# Modbus_TCP.net
KiCad netlist of a schematic drawn in Altium Designer
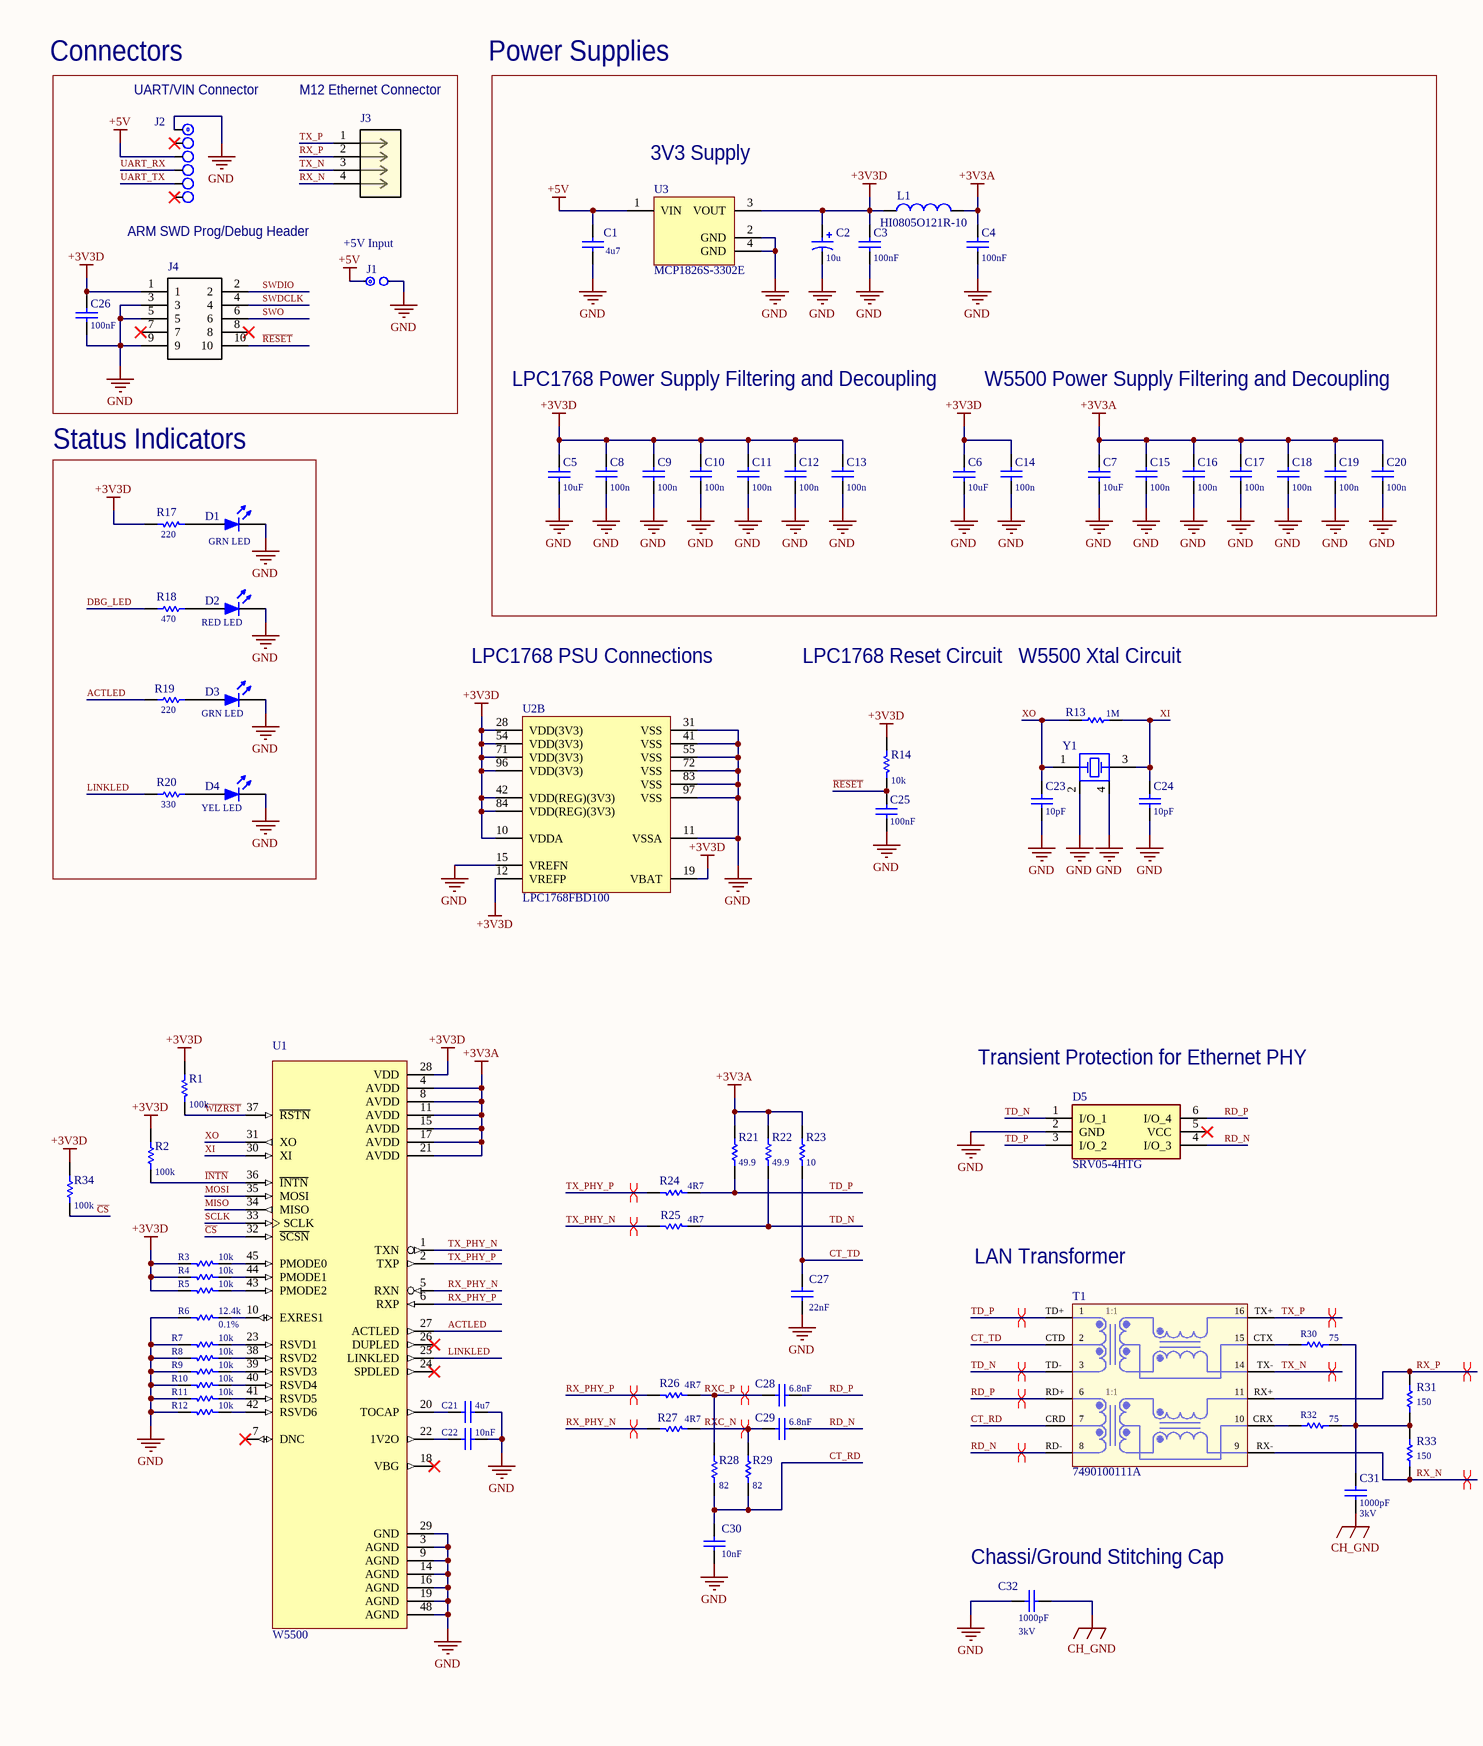
[diagram p0: Modbus TCP.SchDoc, left]
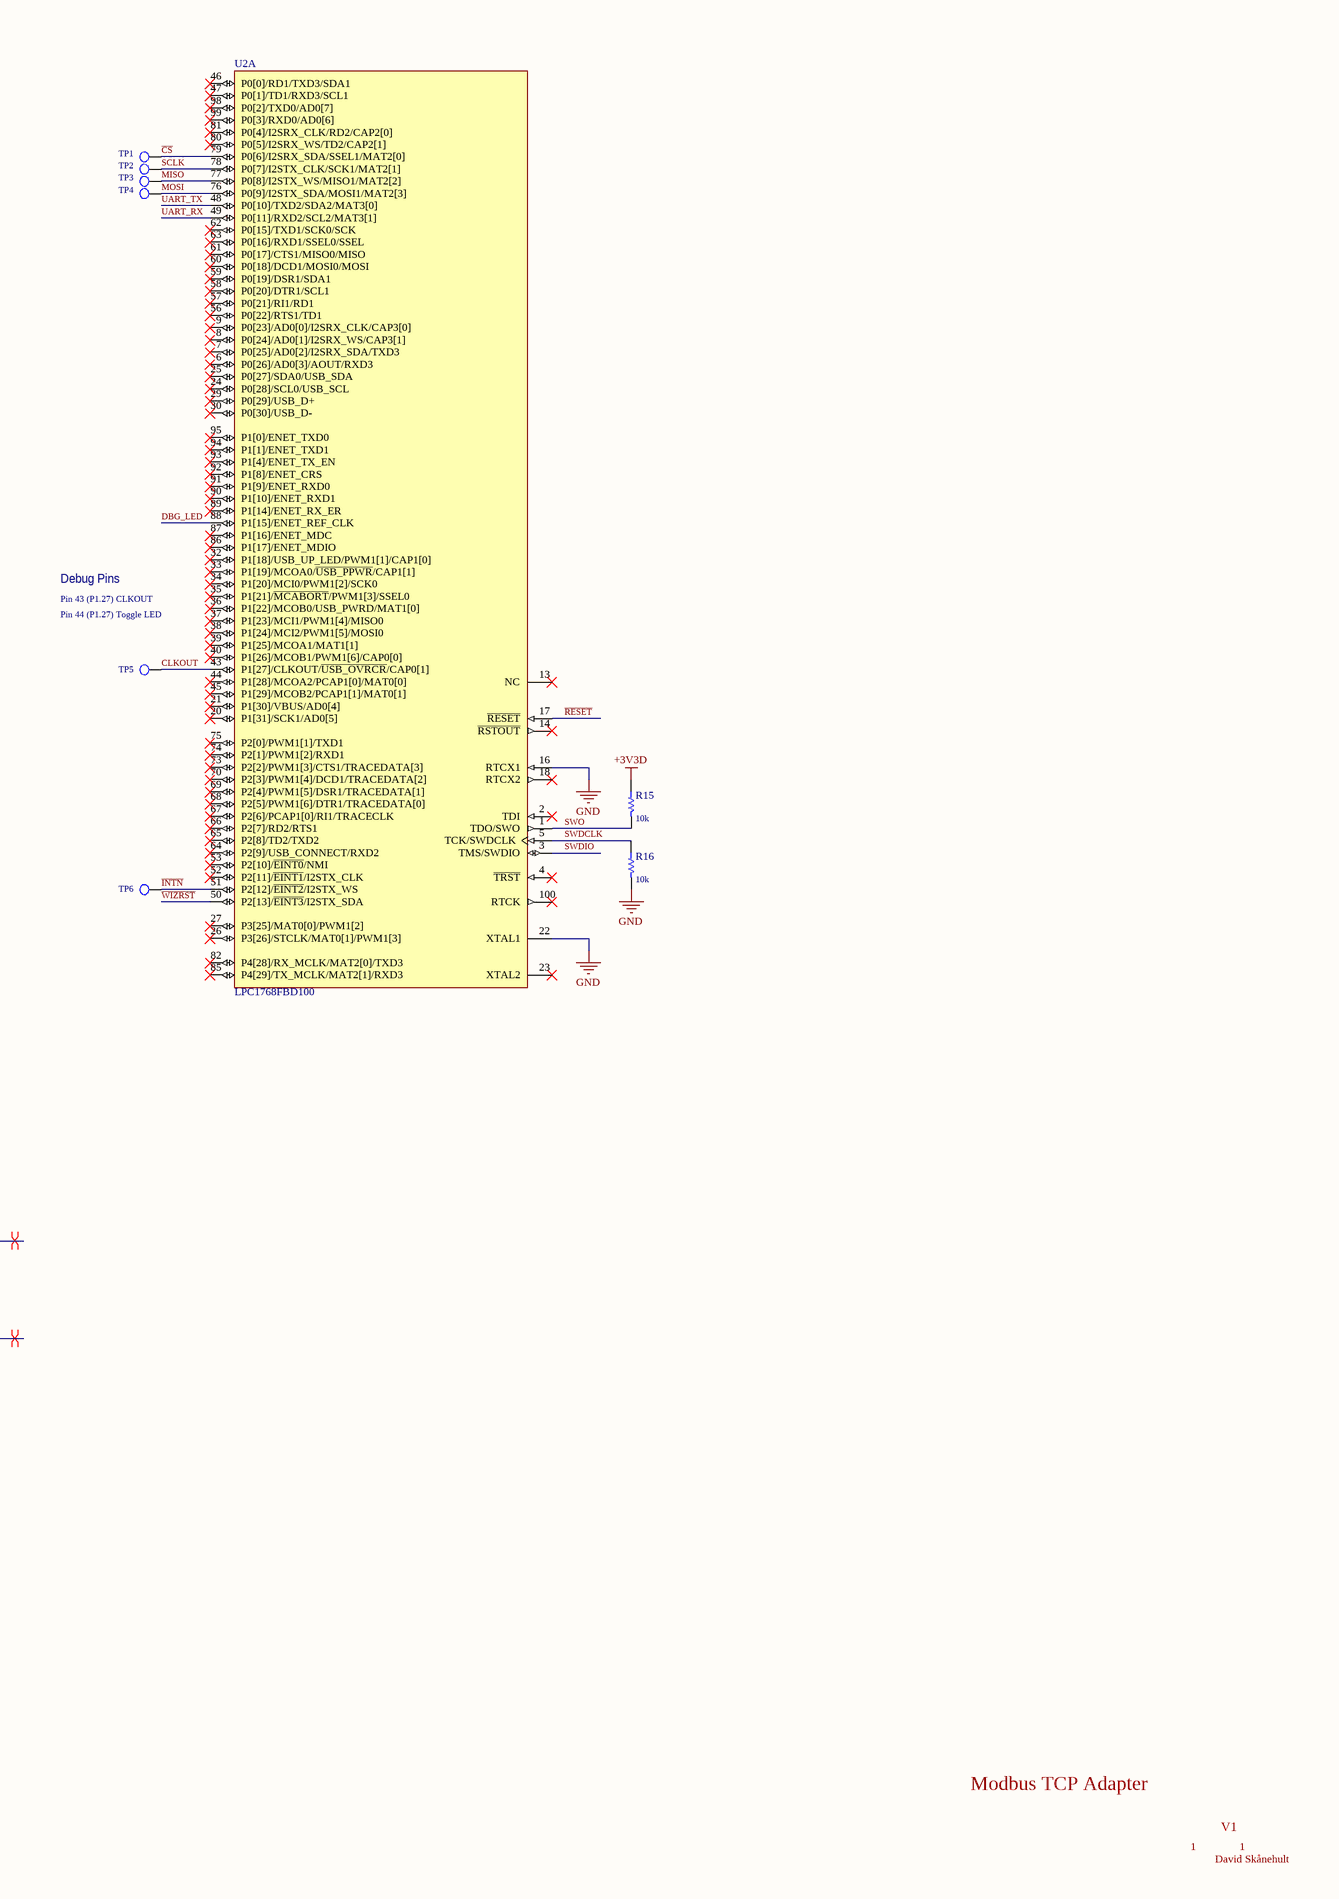
[diagram p1: Modbus TCP.SchDoc, right]

(export (version "E")
  (design (tool "Eeschema 10.0.6"))
  (components
    (comp (ref "C1")
      (value "4u7")
      (footprint "C0805C475K4RACTU")
      (description "CAP, CERM, 4.7 uF, 16 V, +/- 10%, X7R, 0805")
      (fields (field (name "PARTNUMBER") "C0805C475K4RACTU") (field (name "Comment") "CAP_0805-2012"))
      (libsource (lib "RCL") (part "CAP_0805-2012"))
    )
    (comp (ref "C2")
      (value "10u")
      (footprint "CAP3528")
      (description "CAP, TANT, 10 uF, 16 V, +/- 20%, MnO2, 3528")
      (fields
        (field (name "PARTNUMBER") "T494B106M016AT")
        (field (name "Comment") "CAP_TANT")
        (field (name "PUBLISHER") "Altium Limited")
      )
      (libsource (lib "RCL") (part "CAP_TANT"))
    )
    (comp (ref "C3")
      (value "100nF, 16V")
      (footprint "WURTH-CSGP_0402")
      (description "WCAP-CSGP General Purpose Ceramic Capacitors, size 0402, 100nF, +/-10%, 16VDC")
      (fields
        (field (name "PART NUMBER") "885012205037")
        (field (name "CAPACITANCE") "100nF")
        (field (name "PUBLISHER") "Wurth Elektronik")
      )
      (libsource (lib "WCAP-CSGP_rev19a") (part "885012205037"))
    )
    (comp (ref "C4")
      (value "100nF, 16V")
      (footprint "WURTH-CSGP_0402")
      (description "WCAP-CSGP General Purpose Ceramic Capacitors, size 0402, 100nF, +/-10%, 16VDC")
      (fields
        (field (name "PART NUMBER") "885012205037")
        (field (name "CAPACITANCE") "100nF")
        (field (name "PUBLISHER") "Wurth Elektronik")
      )
      (libsource (lib "WCAP-CSGP_rev19a") (part "885012205037"))
    )
    (comp (ref "C5")
      (value "10uF")
      (footprint "C0805C475K3RACAUTO")
      (description "CAP, CERM, 10 uF, 16 V, +/- 10%, X5R, 0805")
      (fields (field (name "PARTNUMBER") "C0805C106K4PACTU") (field (name "Comment") "CAP_0805-2012"))
      (libsource (lib "RCL") (part "CAP_0805-2012"))
    )
    (comp (ref "C6")
      (value "10uF")
      (footprint "C0805C475K3RACAUTO")
      (description "CAP, CERM, 10 uF, 16 V, +/- 10%, X5R, 0805")
      (fields (field (name "PARTNUMBER") "C0805C106K4PACTU") (field (name "Comment") "CAP_0805-2012"))
      (libsource (lib "RCL") (part "CAP_0805-2012"))
    )
    (comp (ref "C7")
      (value "10uF")
      (footprint "C0805C475K3RACAUTO")
      (description "CAP, CERM, 10 uF, 16 V, +/- 10%, X5R, 0805")
      (fields (field (name "PARTNUMBER") "C0805C106K4PACTU") (field (name "Comment") "CAP_0805-2012"))
      (libsource (lib "RCL") (part "CAP_0805-2012"))
    )
    (comp (ref "C8")
      (value "100nF, 16V")
      (footprint "WURTH-CSGP_0402")
      (description "WCAP-CSGP General Purpose Ceramic Capacitors, size 0402, 100nF, +/-10%, 16VDC")
      (fields
        (field (name "PART NUMBER") "885012205037")
        (field (name "CAPACITANCE") "100n")
        (field (name "PUBLISHER") "Wurth Elektronik")
      )
      (libsource (lib "WCAP-CSGP_rev19a") (part "885012205037"))
    )
    (comp (ref "C9")
      (value "100nF, 16V")
      (footprint "WURTH-CSGP_0402")
      (description "WCAP-CSGP General Purpose Ceramic Capacitors, size 0402, 100nF, +/-10%, 16VDC")
      (fields
        (field (name "PART NUMBER") "885012205037")
        (field (name "CAPACITANCE") "100n")
        (field (name "PUBLISHER") "Wurth Elektronik")
      )
      (libsource (lib "WCAP-CSGP_rev19a") (part "885012205037"))
    )
    (comp (ref "C10")
      (value "100nF, 16V")
      (footprint "WURTH-CSGP_0402")
      (description "WCAP-CSGP General Purpose Ceramic Capacitors, size 0402, 100nF, +/-10%, 16VDC")
      (fields
        (field (name "PART NUMBER") "885012205037")
        (field (name "CAPACITANCE") "100n")
        (field (name "PUBLISHER") "Wurth Elektronik")
      )
      (libsource (lib "WCAP-CSGP_rev19a") (part "885012205037"))
    )
    (comp (ref "C11")
      (value "100nF, 16V")
      (footprint "WURTH-CSGP_0402")
      (description "WCAP-CSGP General Purpose Ceramic Capacitors, size 0402, 100nF, +/-10%, 16VDC")
      (fields
        (field (name "PART NUMBER") "885012205037")
        (field (name "CAPACITANCE") "100n")
        (field (name "PUBLISHER") "Wurth Elektronik")
      )
      (libsource (lib "WCAP-CSGP_rev19a") (part "885012205037"))
    )
    (comp (ref "C12")
      (value "100nF, 16V")
      (footprint "WURTH-CSGP_0402")
      (description "WCAP-CSGP General Purpose Ceramic Capacitors, size 0402, 100nF, +/-10%, 16VDC")
      (fields
        (field (name "PART NUMBER") "885012205037")
        (field (name "CAPACITANCE") "100n")
        (field (name "PUBLISHER") "Wurth Elektronik")
      )
      (libsource (lib "WCAP-CSGP_rev19a") (part "885012205037"))
    )
    (comp (ref "C13")
      (value "100nF, 16V")
      (footprint "WURTH-CSGP_0402")
      (description "WCAP-CSGP General Purpose Ceramic Capacitors, size 0402, 100nF, +/-10%, 16VDC")
      (fields
        (field (name "PART NUMBER") "885012205037")
        (field (name "CAPACITANCE") "100n")
        (field (name "PUBLISHER") "Wurth Elektronik")
      )
      (libsource (lib "WCAP-CSGP_rev19a") (part "885012205037"))
    )
    (comp (ref "C14")
      (value "100nF, 16V")
      (footprint "WURTH-CSGP_0402")
      (description "WCAP-CSGP General Purpose Ceramic Capacitors, size 0402, 100nF, +/-10%, 16VDC")
      (fields
        (field (name "PART NUMBER") "885012205037")
        (field (name "CAPACITANCE") "100n")
        (field (name "PUBLISHER") "Wurth Elektronik")
      )
      (libsource (lib "WCAP-CSGP_rev19a") (part "885012205037"))
    )
    (comp (ref "C15")
      (value "100nF, 16V")
      (footprint "WURTH-CSGP_0402")
      (description "WCAP-CSGP General Purpose Ceramic Capacitors, size 0402, 100nF, +/-10%, 16VDC")
      (fields
        (field (name "PART NUMBER") "885012205037")
        (field (name "CAPACITANCE") "100n")
        (field (name "PUBLISHER") "Wurth Elektronik")
      )
      (libsource (lib "WCAP-CSGP_rev19a") (part "885012205037"))
    )
    (comp (ref "C16")
      (value "100nF, 16V")
      (footprint "WURTH-CSGP_0402")
      (description "WCAP-CSGP General Purpose Ceramic Capacitors, size 0402, 100nF, +/-10%, 16VDC")
      (fields
        (field (name "PART NUMBER") "885012205037")
        (field (name "CAPACITANCE") "100n")
        (field (name "PUBLISHER") "Wurth Elektronik")
      )
      (libsource (lib "WCAP-CSGP_rev19a") (part "885012205037"))
    )
    (comp (ref "C17")
      (value "100nF, 16V")
      (footprint "WURTH-CSGP_0402")
      (description "WCAP-CSGP General Purpose Ceramic Capacitors, size 0402, 100nF, +/-10%, 16VDC")
      (fields
        (field (name "PART NUMBER") "885012205037")
        (field (name "CAPACITANCE") "100n")
        (field (name "PUBLISHER") "Wurth Elektronik")
      )
      (libsource (lib "WCAP-CSGP_rev19a") (part "885012205037"))
    )
    (comp (ref "C18")
      (value "100nF, 16V")
      (footprint "WURTH-CSGP_0402")
      (description "WCAP-CSGP General Purpose Ceramic Capacitors, size 0402, 100nF, +/-10%, 16VDC")
      (fields
        (field (name "PART NUMBER") "885012205037")
        (field (name "CAPACITANCE") "100n")
        (field (name "PUBLISHER") "Wurth Elektronik")
      )
      (libsource (lib "WCAP-CSGP_rev19a") (part "885012205037"))
    )
    (comp (ref "C19")
      (value "100nF, 16V")
      (footprint "WURTH-CSGP_0402")
      (description "WCAP-CSGP General Purpose Ceramic Capacitors, size 0402, 100nF, +/-10%, 16VDC")
      (fields
        (field (name "PART NUMBER") "885012205037")
        (field (name "CAPACITANCE") "100n")
        (field (name "PUBLISHER") "Wurth Elektronik")
      )
      (libsource (lib "WCAP-CSGP_rev19a") (part "885012205037"))
    )
    (comp (ref "C20")
      (value "100nF, 16V")
      (footprint "WURTH-CSGP_0402")
      (description "WCAP-CSGP General Purpose Ceramic Capacitors, size 0402, 100nF, +/-10%, 16VDC")
      (fields
        (field (name "PART NUMBER") "885012205037")
        (field (name "CAPACITANCE") "100n")
        (field (name "PUBLISHER") "Wurth Elektronik")
      )
      (libsource (lib "WCAP-CSGP_rev19a") (part "885012205037"))
    )
    (comp (ref "C21")
      (value "4u7")
      (footprint "C0805C475K4RACTU")
      (description "CAP, CERM, 4.7 uF, 16 V, +/- 10%, X7R, 0805")
      (fields (field (name "PARTNUMBER") "C0805C475K4RACTU") (field (name "Comment") "CAP_0805-2012"))
      (libsource (lib "RCL") (part "CAP_0805-2012"))
    )
    (comp (ref "C22")
      (value "10nF, 25V")
      (footprint "WURTH-CSGP_0402")
      (description "WCAP-CSGP General Purpose Ceramic Capacitors, size 0402, 10nF, +/-10%, 25VDC")
      (fields
        (field (name "PART NUMBER") "885012205050")
        (field (name "CAPACITANCE") "10nF")
        (field (name "PUBLISHER") "Wurth Elektronik")
      )
      (libsource (lib "WCAP-CSGP_rev19a") (part "885012205050"))
    )
    (comp (ref "C23")
      (value "10pF, 25V")
      (footprint "WURTH-CSGP_0402")
      (description "WCAP-CSGP General Purpose Ceramic Capacitors, size 0402, 10pF, +/-5%, 25VDC")
      (fields
        (field (name "PART NUMBER") "885012005040")
        (field (name "CAPACITANCE") "10pF")
        (field (name "PUBLISHER") "Wurth Elektronik")
      )
      (libsource (lib "WCAP-CSGP_rev19a") (part "885012005040"))
    )
    (comp (ref "C24")
      (value "10pF, 25V")
      (footprint "WURTH-CSGP_0402")
      (description "WCAP-CSGP General Purpose Ceramic Capacitors, size 0402, 10pF, +/-5%, 25VDC")
      (fields
        (field (name "PART NUMBER") "885012005040")
        (field (name "CAPACITANCE") "10pF")
        (field (name "PUBLISHER") "Wurth Elektronik")
      )
      (libsource (lib "WCAP-CSGP_rev19a") (part "885012005040"))
    )
    (comp (ref "C25")
      (value "100nF, 16V")
      (footprint "WURTH-CSGP_0402")
      (description "WCAP-CSGP General Purpose Ceramic Capacitors, size 0402, 100nF, +/-10%, 16VDC")
      (fields
        (field (name "PART NUMBER") "885012205037")
        (field (name "CAPACITANCE") "100nF")
        (field (name "PUBLISHER") "Wurth Elektronik")
      )
      (libsource (lib "WCAP-CSGP_rev19a") (part "885012205037"))
    )
    (comp (ref "C26")
      (value "100nF, 16V")
      (footprint "WCAP-CSGP_0402")
      (description "WCAP-CSGP General Purpose Ceramic Capacitors, size 0402, 100nF, +/-10%, 16VDC")
      (fields
        (field (name "PART NUMBER") "885012205037")
        (field (name "CAPACITANCE") "100nF")
        (field (name "PUBLISHER") "Wurth Elektronik")
      )
      (libsource (lib "WCAP-CSGP_rev19a") (part "885012205037"))
    )
    (comp (ref "C27")
      (value "22nF, 25V")
      (footprint "WURTH-CSGP_0402")
      (description "WCAP-CSGP General Purpose Ceramic Capacitors, size 0402, 22nF, +/-10%, 25VDC")
      (fields
        (field (name "PART NUMBER") "885012205052")
        (field (name "CAPACITANCE") "22nF")
        (field (name "PUBLISHER") "Wurth Elektronik")
      )
      (libsource (lib "WCAP-CSGP_rev19a") (part "885012205052"))
    )
    (comp (ref "C28")
      (value "6.8nF, 50V")
      (footprint "WURTH-CSGP_0603_Reflow")
      (description "WCAP-CSGP General Purpose Ceramic Capacitors, size 0603, 6.8nF, +/-10%, 50VDC")
      (fields
        (field (name "PART NUMBER") "885012206088")
        (field (name "CAPACITANCE") "6.8nF")
        (field (name "PUBLISHER") "Wurth Elektronik")
      )
      (libsource (lib "WCAP-CSGP_rev19a") (part "885012206088"))
    )
    (comp (ref "C29")
      (value "6.8nF, 50V")
      (footprint "WURTH-CSGP_0603_Reflow")
      (description "WCAP-CSGP General Purpose Ceramic Capacitors, size 0603, 6.8nF, +/-10%, 50VDC")
      (fields
        (field (name "PART NUMBER") "885012206088")
        (field (name "CAPACITANCE") "6.8nF")
        (field (name "PUBLISHER") "Wurth Elektronik")
      )
      (libsource (lib "WCAP-CSGP_rev19a") (part "885012206088"))
    )
    (comp (ref "C30")
      (value "10nF, 25V")
      (footprint "WURTH-CSGP_0402")
      (description "WCAP-CSGP General Purpose Ceramic Capacitors, size 0402, 10nF, +/-10%, 25VDC")
      (fields
        (field (name "PART NUMBER") "885012205050")
        (field (name "CAPACITANCE") "10nF")
        (field (name "PUBLISHER") "Wurth Elektronik")
      )
      (libsource (lib "WCAP-CSGP_rev19a") (part "885012205050"))
    )
    (comp (ref "C31")
      (value "1000pF")
      (footprint "C1812C102KHRACTU")
      (description "CAP, CERM, 1000 pF, 3 kV, +/- 10%, X7R, 1812")
      (fields
        (field (name "VALUE2") "3kV")
        (field (name "PARTNUMBER") "C1812C102KHRACTU")
        (field (name "Comment") "CAP_1812-4532")
      )
      (libsource (lib "RCL") (part "CAP_1812-4532"))
    )
    (comp (ref "C32")
      (value "1000pF")
      (footprint "C1812C102KHRACTU")
      (description "CAP, CERM, 1000 pF, 3 kV, +/- 10%, X7R, 1812")
      (fields
        (field (name "VALUE2") "3kV")
        (field (name "PARTNUMBER") "C1812C102KHRACTU")
        (field (name "Comment") "CAP_1812-4532")
      )
      (libsource (lib "RCL") (part "CAP_1812-4532"))
    )
    (comp (ref "D1")
      (value "GRN LED")
      (footprint "KPG-1608")
      (description "KPG-1608CGKC-T")
      (fields (field (name "PUBLISHER") "Altium Limited"))
      (libsource (lib "Diodes") (part "LED"))
    )
    (comp (ref "D2")
      (value "RED LED")
      (footprint "KPG-1608")
      (description "KPG-1608SURKC-T")
      (fields (field (name "PUBLISHER") "Altium Limited"))
      (libsource (lib "Diodes") (part "LED"))
    )
    (comp (ref "D3")
      (value "GRN LED")
      (footprint "KPG-1608")
      (description "KPG-1608CGKC-T")
      (fields (field (name "PUBLISHER") "Altium Limited"))
      (libsource (lib "Diodes") (part "LED"))
    )
    (comp (ref "D4")
      (value "YEL LED")
      (footprint "KPG-1608")
      (fields (field (name "PARTNUMBER") "KPG-1608SYKC-T") (field (name "PUBLISHER") "Altium Limited"))
      (libsource (lib "Diodes") (part "LED"))
    )
    (comp (ref "D5")
      (value "SRV05-4HTG")
      (footprint "SamacSys:SOT95P280X145-6N")
      (description "TVS Diode (Uni-directional)")
      (fields (field (name "RS PART NUMBER") "7931986P"))
      (libsource (lib "*") (part "SRV05-4HTG"))
    )
    (comp (ref "J1") (value "+5V Input") (footprint "J1x2") (libsource (lib "Connektor") (part "H-1x2")))
    (comp (ref "J2")
      (value "UART/VIN Connector")
      (footprint "HR-1x6")
      (libsource (lib "Connektor") (part "HR-1x6"))
    )
    (comp (ref "J3")
      (value "M12 Ethernet Connector")
      (footprint "CONN4_T414351204")
      (description "M12,FRONT MOUNTING,FEMALE,D CODE,4P")
      (fields
        (field (name "PARTNUMBER") "T4143512041-000")
        (field (name "COPYRIGHT") "Copyright (C) 2016 Accelerated Designs. All rights reserved")
      )
      (libsource (lib "T4143512041-000") (part "T4143512041-000"))
    )
    (comp (ref "J4")
      (value "ARM SWD Prog/Debug Header")
      (footprint "*SAMTEC_FTSH-105-01-L-DV-K")
      (description "FTSH Series .050 Micro Terminal Strip")
      (fields (field (name "MF") "Samtec") (field (name "PARTNUMBER") "FTSH-105-01-L-DV-K"))
      (libsource (lib "FTSH-105-01-L-DV-K") (part "FTSH-105-01-L-DV-K"))
    )
    (comp (ref "L1")
      (value "HI0805O121R-10")
      (footprint "HI0805O121R-10")
      (description "Laird HI0805O121R-10 Ferrite Bead")
      (libsource (lib "RCL") (part "FERRITE"))
    )
    (comp (ref "R1")
      (value "100k")
      (footprint "RESC1005N - PANASONIC")
      (description "RES, 100 k, 1%, 0.1 W, 0402")
      (fields (field (name "PARTNUMBER") "ERJ2RKF1003X") (field (name "Comment") "RES_0402-1005"))
      (libsource (lib "RCL") (part "RES_0402-1005"))
    )
    (comp (ref "R2")
      (value "100k")
      (footprint "RESC1005N - PANASONIC")
      (description "RES, 100 k, 1%, 0.1 W, 0402")
      (fields (field (name "PARTNUMBER") "ERJ2RKF1003X") (field (name "Comment") "RES_0402-1005"))
      (libsource (lib "RCL") (part "RES_0402-1005"))
    )
    (comp (ref "R3")
      (value "10k")
      (footprint "RESC1005N - PANASONIC")
      (description "RES, 10 k, 1%, 0.1 W, 0402")
      (fields (field (name "PARTNUMBER") "ERJ2RKF1002X") (field (name "Comment") "RES_0402-1005"))
      (libsource (lib "RCL") (part "RES_0402-1005"))
    )
    (comp (ref "R4")
      (value "10k")
      (footprint "RESC1005N - PANASONIC")
      (description "RES, 10 k, 1%, 0.1 W, 0402")
      (fields (field (name "PARTNUMBER") "ERJ2RKF1002X") (field (name "Comment") "RES_0402-1005"))
      (libsource (lib "RCL") (part "RES_0402-1005"))
    )
    (comp (ref "R5")
      (value "10k")
      (footprint "RESC1005N - PANASONIC")
      (description "RES, 10 k, 1%, 0.1 W, 0402")
      (fields (field (name "PARTNUMBER") "ERJ2RKF1002X") (field (name "Comment") "RES_0402-1005"))
      (libsource (lib "RCL") (part "RES_0402-1005"))
    )
    (comp (ref "R6")
      (value "12.4k")
      (footprint "RESC1608N - PANASONIC ERJ")
      (description "RES, 12.4 k, 0.1%, 0.1 W, 0603")
      (fields
        (field (name "VALUE2") "0.1%")
        (field (name "PARTNUMBER") "ERA3AEB1242V")
        (field (name "Comment") "RES_0603-1608")
      )
      (libsource (lib "RCL") (part "RES_0603-1608"))
    )
    (comp (ref "R7")
      (value "10k")
      (footprint "RESC1005N - PANASONIC")
      (description "RES, 10 k, 1%, 0.1 W, 0402")
      (fields (field (name "PARTNUMBER") "ERJ2RKF1002X") (field (name "Comment") "RES_0402-1005"))
      (libsource (lib "RCL") (part "RES_0402-1005"))
    )
    (comp (ref "R8")
      (value "10k")
      (footprint "RESC1005N - PANASONIC")
      (description "RES, 10 k, 1%, 0.1 W, 0402")
      (fields (field (name "PARTNUMBER") "ERJ2RKF1002X") (field (name "Comment") "RES_0402-1005"))
      (libsource (lib "RCL") (part "RES_0402-1005"))
    )
    (comp (ref "R9")
      (value "10k")
      (footprint "RESC1005N - PANASONIC")
      (description "RES, 10 k, 1%, 0.1 W, 0402")
      (fields (field (name "PARTNUMBER") "ERJ2RKF1002X") (field (name "Comment") "RES_0402-1005"))
      (libsource (lib "RCL") (part "RES_0402-1005"))
    )
    (comp (ref "R10")
      (value "10k")
      (footprint "RESC1005N - PANASONIC")
      (description "RES, 10 k, 1%, 0.1 W, 0402")
      (fields (field (name "PARTNUMBER") "ERJ2RKF1002X") (field (name "Comment") "RES_0402-1005"))
      (libsource (lib "RCL") (part "RES_0402-1005"))
    )
    (comp (ref "R11")
      (value "10k")
      (footprint "RESC1005N - PANASONIC")
      (description "RES, 10 k, 1%, 0.1 W, 0402")
      (fields (field (name "PARTNUMBER") "ERJ2RKF1002X") (field (name "Comment") "RES_0402-1005"))
      (libsource (lib "RCL") (part "RES_0402-1005"))
    )
    (comp (ref "R12")
      (value "10k")
      (footprint "RESC1005N - PANASONIC")
      (description "RES, 10 k, 1%, 0.1 W, 0402")
      (fields (field (name "PARTNUMBER") "ERJ2RKF1002X") (field (name "Comment") "RES_0402-1005"))
      (libsource (lib "RCL") (part "RES_0402-1005"))
    )
    (comp (ref "R13")
      (value "1M")
      (footprint "RESC1005N - PANASONIC")
      (description "RES, 1 Meg, 1%, 0.1 W, 0402")
      (fields (field (name "PARTNUMBER") "ERJ2RKF1004X") (field (name "Comment") "RES_0402-1005"))
      (libsource (lib "RCL") (part "RES_0402-1005"))
    )
    (comp (ref "R14")
      (value "10k")
      (footprint "RESC1005N - PANASONIC")
      (description "RES, 10 k, 1%, 0.1 W, 0402")
      (fields (field (name "PARTNUMBER") "ERJ2RKF1002X") (field (name "Comment") "RES_0402-1005"))
      (libsource (lib "RCL") (part "RES_0402-1005"))
    )
    (comp (ref "R15")
      (value "10k")
      (footprint "RESC1005N - PANASONIC")
      (description "RES, 10 k, 1%, 0.1 W, 0402")
      (fields (field (name "PARTNUMBER") "ERJ2RKF1002X") (field (name "Comment") "RES_0402-1005"))
      (libsource (lib "RCL") (part "RES_0402-1005"))
    )
    (comp (ref "R16")
      (value "10k")
      (footprint "RESC1005N - PANASONIC")
      (description "RES, 10 k, 1%, 0.1 W, 0402")
      (fields (field (name "PARTNUMBER") "ERJ2RKF1002X") (field (name "Comment") "RES_0402-1005"))
      (libsource (lib "RCL") (part "RES_0402-1005"))
    )
    (comp (ref "R17")
      (value "220")
      (footprint "RESC1005N - PANASONIC")
      (description "RES, 220, 1%, 0.1 W, 0402")
      (fields (field (name "PARTNUMBER") "ERJ2RKF2200X") (field (name "Comment") "RES_0402-1005"))
      (libsource (lib "RCL") (part "RES_0402-1005"))
    )
    (comp (ref "R18")
      (value "470")
      (footprint "RESC1005N - PANASONIC")
      (description "RES, 470, 1%, 0.1 W, 0402")
      (fields (field (name "PARTNUMBER") "ERJ2RKF4700X") (field (name "Comment") "RES_0402-1005"))
      (libsource (lib "RCL") (part "RES_0402-1005"))
    )
    (comp (ref "R19")
      (value "220")
      (footprint "RESC1005N - PANASONIC")
      (description "RES, 220, 1%, 0.1 W, 0402")
      (fields (field (name "PARTNUMBER") "ERJ2RKF2200X") (field (name "Comment") "RES_0402-1005"))
      (libsource (lib "RCL") (part "RES_0402-1005"))
    )
    (comp (ref "R20")
      (value "330")
      (footprint "RESC1005N - PANASONIC")
      (description "RES, 220, 1%, 0.1 W, 0402")
      (fields (field (name "PARTNUMBER") "ERJ2RKF3300X") (field (name "Comment") "RES_0402-1005"))
      (libsource (lib "RCL") (part "RES_0402-1005"))
    )
    (comp (ref "R21")
      (value "49.9")
      (footprint "RESC1005N - PANASONIC")
      (description "RES, 49.9, 1%, 0.1 W, 0402")
      (fields (field (name "PARTNUMBER") "ERJ2RKF49R9X") (field (name "Comment") "RES_0402-1005"))
      (libsource (lib "RCL") (part "RES_0402-1005"))
    )
    (comp (ref "R22")
      (value "49.9")
      (footprint "RESC1005N - PANASONIC")
      (description "RES, 49.9, 1%, 0.1 W, 0402")
      (fields (field (name "PARTNUMBER") "ERJ2RKF49R9X") (field (name "Comment") "RES_0402-1005"))
      (libsource (lib "RCL") (part "RES_0402-1005"))
    )
    (comp (ref "R23")
      (value "10")
      (footprint "RESC1005N - PANASONIC")
      (description "RES, 10, 1%, 0.1 W, 0402")
      (fields (field (name "Comment") "RES_0402-1005"))
      (libsource (lib "RCL") (part "RES_0402-1005"))
    )
    (comp (ref "R24")
      (value "4R7")
      (footprint "RESC1005N - PANASONIC")
      (description "RES, 4R7, 1%, 0.1 W, 0402")
      (fields (field (name "PARTNUMBER") "CRCW04024R70FKEDHP") (field (name "Comment") "RES_0402-1005"))
      (libsource (lib "RCL") (part "RES_0402-1005"))
    )
    (comp (ref "R25")
      (value "4R7")
      (footprint "RESC1005N - PANASONIC")
      (description "RES, 4R7, 1%, 0.1 W, 0402")
      (fields (field (name "PARTNUMBER") "CRCW04024R70FKEDHP") (field (name "Comment") "RES_0402-1005"))
      (libsource (lib "RCL") (part "RES_0402-1005"))
    )
    (comp (ref "R26")
      (value "4R7")
      (footprint "RESC1005N - PANASONIC")
      (description "RES, 4R7, 1%, 0.1 W, 0402")
      (fields (field (name "PARTNUMBER") "CRCW04024R70FKEDHP") (field (name "Comment") "RES_0402-1005"))
      (libsource (lib "RCL") (part "RES_0402-1005"))
    )
    (comp (ref "R27")
      (value "4R7")
      (footprint "RESC1005N - PANASONIC")
      (description "RES, 4R7, 1%, 0.1 W, 0402")
      (fields (field (name "PARTNUMBER") "CRCW04024R70FKEDHP") (field (name "Comment") "RES_0402-1005"))
      (libsource (lib "RCL") (part "RES_0402-1005"))
    )
    (comp (ref "R28")
      (value "82")
      (footprint "RESC1005N - PANASONIC")
      (description "0402 Resistor")
      (fields (field (name "PARTNUMBER") "ERJ2RKF82R0X") (field (name "Comment") "RES_0402-1005"))
      (libsource (lib "RCL") (part "RES_0402-1005"))
    )
    (comp (ref "R29")
      (value "82")
      (footprint "RESC1005N - PANASONIC")
      (description "0402 Resistor")
      (fields (field (name "PARTNUMBER") "ERJ2RKF82R0X") (field (name "Comment") "RES_0402-1005"))
      (libsource (lib "RCL") (part "RES_0402-1005"))
    )
    (comp (ref "R30")
      (value "75")
      (footprint "RESC1608N - PANASONIC ERJ")
      (description "RES, 75, 1%, 0.1 W, 0603")
      (fields (field (name "PARTNUMBER") "CRCW060375R0FKEA") (field (name "Comment") "RES_0603-1608"))
      (libsource (lib "RCL") (part "RES_0603-1608"))
    )
    (comp (ref "R31")
      (value "150")
      (footprint "RESC1608N - PANASONIC ERJ")
      (description "RES, 150, 1%, 0.1 W, 0603")
      (fields (field (name "PARTNUMBER") "CRCW0603150RFKEA") (field (name "Comment") "RES_0603-1608"))
      (libsource (lib "RCL") (part "RES_0603-1608"))
    )
    (comp (ref "R32")
      (value "75")
      (footprint "RESC1608N - PANASONIC ERJ")
      (description "RES, 75, 1%, 0.1 W, 0603")
      (fields (field (name "PARTNUMBER") "CRCW060375R0FKEA") (field (name "Comment") "RES_0603-1608"))
      (libsource (lib "RCL") (part "RES_0603-1608"))
    )
    (comp (ref "R33")
      (value "150")
      (footprint "RESC1608N - PANASONIC ERJ")
      (description "RES, 150, 1%, 0.1 W, 0603")
      (fields (field (name "PARTNUMBER") "CRCW0603150RFKEA") (field (name "Comment") "RES_0603-1608"))
      (libsource (lib "RCL") (part "RES_0603-1608"))
    )
    (comp (ref "R34")
      (value "100k")
      (footprint "RESC1005N - PANASONIC")
      (description "RES, 100 k, 1%, 0.1 W, 0402")
      (fields (field (name "PARTNUMBER") "ERJ2RKF1003X") (field (name "Comment") "RES_0402-1005"))
      (libsource (lib "RCL") (part "RES_0402-1005"))
    )
    (comp (ref "T1")
      (value "7490100111A")
      (footprint "7490100111A")
      (description "WE-LAN LAN Transformer, SMT, 10/100 Base-T, 1 Port, non-PoE")
      (fields (field (name "PUBLISHER") "Wurth Elektronik"))
      (libsource (lib "WE-LAN") (part "7490100111A"))
    )
    (comp (ref "TP1")
      (value "Test Point")
      (footprint "TEST_PAD")
      (description "Test Pad")
      (fields (field (name "PUBLISHER") "Altium Limited"))
      (libsource (lib "Projekt2") (part "Test Point"))
    )
    (comp (ref "TP2")
      (value "Test Point")
      (footprint "TEST_PAD")
      (description "Test Pad")
      (fields (field (name "PUBLISHER") "Altium Limited"))
      (libsource (lib "Projekt2") (part "Test Point"))
    )
    (comp (ref "TP3")
      (value "Test Point")
      (footprint "TEST_PAD")
      (description "Test Pad")
      (fields (field (name "PUBLISHER") "Altium Limited"))
      (libsource (lib "Projekt2") (part "Test Point"))
    )
    (comp (ref "TP4")
      (value "Test Point")
      (footprint "TEST_PAD")
      (description "Test Pad")
      (fields (field (name "PUBLISHER") "Altium Limited"))
      (libsource (lib "Projekt2") (part "Test Point"))
    )
    (comp (ref "TP5")
      (value "Test Point")
      (footprint "TEST_PAD")
      (description "Test Pad")
      (fields (field (name "PUBLISHER") "Altium Limited"))
      (libsource (lib "Projekt2") (part "Test Point"))
    )
    (comp (ref "TP6")
      (value "Test Point")
      (footprint "TEST_PAD")
      (description "Test Pad")
      (fields (field (name "PUBLISHER") "Altium Limited"))
      (libsource (lib "Projekt2") (part "Test Point"))
    )
    (comp (ref "U1")
      (value "W5500")
      (footprint "*QFP50P900X900X160-48N")
      (description "Ethernet Controller 10/100 Base-T/TX MAC PHY SPI QFP48")
      (fields (field (name "MF") "WIZnet"))
      (libsource (lib "W5500") (part "W5500"))
    )
    (comp (ref "U2")
      (value "LPC1768FBD100")
      (footprint "SOT407-1_V")
      (libsource (lib "NXP Semiconductors Cortex-M3") (part "LPC1768FBD100"))
    )
    (comp (ref "U3")
      (value "MCP1826S-3302E")
      (footprint "SOT-223-DB3_N")
      (description "1000 mA, Low Voltage, Low Quiescent Current LDO Regulator, 3-Pin SOT-223, Extended Temperature")
      (fields (field (name "MANUFACTURER") "Microchip") (field (name "PARTNUMBER") "MCP1826S-3302E/DB"))
      (libsource (lib "Microchip Power Management Line Regulator") (part "MCP1826S-3302E/DB"))
    )
    (comp (ref "Y1")
      (value "XTAL 4-pin")
      (footprint "IQXC-42")
      (description "Crystal Oscillator")
      (fields (field (name "PARTNUMBER") "LFXTAL069494") (field (name "PUBLISHER") "Altium Limited"))
      (libsource (lib "Miscellaneous Devices") (part "XTAL 4-pin"))
    )
  )
  (nets
    (net (code "1") (name "+3V3A") (class "Default")
      (node (ref "C15") (pin "1") (pinfunction "1_1") (pintype "passive"))
      (node (ref "C16") (pin "1") (pinfunction "1_1") (pintype "passive"))
      (node (ref "C17") (pin "1") (pinfunction "1_1") (pintype "passive"))
      (node (ref "C18") (pin "1") (pinfunction "1_1") (pintype "passive"))
      (node (ref "C19") (pin "1") (pinfunction "1_1") (pintype "passive"))
      (node (ref "C20") (pin "1") (pinfunction "1_1") (pintype "passive"))
      (node (ref "C4") (pin "1") (pinfunction "1_1") (pintype "passive"))
      (node (ref "C7") (pin "1") (pinfunction "1_1") (pintype "passive"))
      (node (ref "L1") (pin "2") (pinfunction "2_2") (pintype "passive"))
      (node (ref "R21") (pin "1") (pinfunction "1_1") (pintype "passive"))
      (node (ref "R22") (pin "1") (pinfunction "1_1") (pintype "passive"))
      (node (ref "R23") (pin "1") (pinfunction "1_1") (pintype "passive"))
      (node (ref "U1") (pin "11") (pinfunction "AVDD_11") (pintype "power_in"))
      (node (ref "U1") (pin "15") (pinfunction "AVDD_15") (pintype "power_in"))
      (node (ref "U1") (pin "17") (pinfunction "AVDD_17") (pintype "power_in"))
      (node (ref "U1") (pin "21") (pinfunction "AVDD_21") (pintype "power_in"))
      (node (ref "U1") (pin "4") (pinfunction "AVDD_4") (pintype "power_in"))
      (node (ref "U1") (pin "8") (pinfunction "AVDD_8") (pintype "power_in"))
    )
    (net (code "2") (name "+3V3D") (class "Default")
      (node (ref "C10") (pin "1") (pinfunction "1_1") (pintype "passive"))
      (node (ref "C11") (pin "1") (pinfunction "1_1") (pintype "passive"))
      (node (ref "C12") (pin "1") (pinfunction "1_1") (pintype "passive"))
      (node (ref "C13") (pin "1") (pinfunction "1_1") (pintype "passive"))
      (node (ref "C14") (pin "1") (pinfunction "1_1") (pintype "passive"))
      (node (ref "C2") (pin "2") (pinfunction "2_2") (pintype "passive"))
      (node (ref "C26") (pin "1") (pinfunction "1_1") (pintype "passive"))
      (node (ref "C3") (pin "1") (pinfunction "1_1") (pintype "passive"))
      (node (ref "C5") (pin "1") (pinfunction "1_1") (pintype "passive"))
      (node (ref "C6") (pin "1") (pinfunction "1_1") (pintype "passive"))
      (node (ref "C8") (pin "1") (pinfunction "1_1") (pintype "passive"))
      (node (ref "C9") (pin "1") (pinfunction "1_1") (pintype "passive"))
      (node (ref "J4") (pin "1") (pinfunction "1_1") (pintype "passive"))
      (node (ref "L1") (pin "1") (pinfunction "1_1") (pintype "passive"))
      (node (ref "R1") (pin "1") (pinfunction "1_1") (pintype "passive"))
      (node (ref "R14") (pin "1") (pinfunction "1_1") (pintype "passive"))
      (node (ref "R15") (pin "1") (pinfunction "1_1") (pintype "passive"))
      (node (ref "R17") (pin "2") (pinfunction "2_2") (pintype "passive"))
      (node (ref "R2") (pin "1") (pinfunction "1_1") (pintype "passive"))
      (node (ref "R3") (pin "2") (pinfunction "2_2") (pintype "passive"))
      (node (ref "R34") (pin "1") (pinfunction "1_1") (pintype "passive"))
      (node (ref "R4") (pin "2") (pinfunction "2_2") (pintype "passive"))
      (node (ref "R5") (pin "2") (pinfunction "2_2") (pintype "passive"))
      (node (ref "U1") (pin "28") (pinfunction "VDD_28") (pintype "power_in"))
      (node (ref "U2") (pin "10") (pinfunction "VDDA_10") (pintype "power_in"))
      (node (ref "U2") (pin "12") (pinfunction "VREFP_12") (pintype "power_in"))
      (node (ref "U2") (pin "19") (pinfunction "VBAT_19") (pintype "power_in"))
      (node (ref "U2") (pin "28") (pinfunction "VDD(3V3)_28") (pintype "power_in"))
      (node (ref "U2") (pin "42") (pinfunction "VDD(REG)(3V3)_42") (pintype "power_in"))
      (node (ref "U2") (pin "54") (pinfunction "VDD(3V3)_54") (pintype "power_in"))
      (node (ref "U2") (pin "71") (pinfunction "VDD(3V3)_71") (pintype "power_in"))
      (node (ref "U2") (pin "84") (pinfunction "VDD(REG)(3V3)_84") (pintype "power_in"))
      (node (ref "U2") (pin "96") (pinfunction "VDD(3V3)_96") (pintype "power_in"))
      (node (ref "U3") (pin "3") (pinfunction "VOUT_3") (pintype "power_in"))
    )
    (net (code "3") (name "+5V") (class "Default")
      (node (ref "C1") (pin "1") (pinfunction "1_1") (pintype "passive"))
      (node (ref "J1") (pin "1") (pinfunction "1_1") (pintype "passive"))
      (node (ref "J2") (pin "3") (pinfunction "3_3") (pintype "passive"))
      (node (ref "U3") (pin "1") (pinfunction "VIN_1") (pintype "power_in"))
    )
    (net (code "4") (name "/ACTLED") (class "Default")
      (node (ref "R19") (pin "1") (pinfunction "1_1") (pintype "passive"))
      (node (ref "U1") (pin "27") (pinfunction "ACTLED_27") (pintype "output"))
    )
    (net (code "5") (name "/CLKOUT") (class "Default")
      (node (ref "TP5") (pin "1") (pinfunction "1_1") (pintype "passive"))
      (node (ref "U2") (pin "43") (pinfunction "P1[27]/CLKOUT/~{USB_OVRCR}/CAP0[1]_43") (pintype "bidirectional"))
    )
    (net (code "6") (name "/CT_RD") (class "Default")
      (node (ref "C30") (pin "1") (pinfunction "1_1") (pintype "passive"))
      (node (ref "R28") (pin "1") (pinfunction "1_1") (pintype "passive"))
      (node (ref "R29") (pin "1") (pinfunction "1_1") (pintype "passive"))
      (node (ref "T1") (pin "7") (pinfunction "CRD_7") (pintype "passive"))
    )
    (net (code "7") (name "/CT_TD") (class "Default")
      (node (ref "C27") (pin "1") (pinfunction "1_1") (pintype "passive"))
      (node (ref "R23") (pin "2") (pinfunction "2_2") (pintype "passive"))
      (node (ref "T1") (pin "2") (pinfunction "CTD_2") (pintype "passive"))
    )
    (net (code "8") (name "/DBG_LED") (class "Default")
      (node (ref "R18") (pin "1") (pinfunction "1_1") (pintype "passive"))
      (node (ref "U2") (pin "88") (pinfunction "P1[15]/ENET_REF_CLK_88") (pintype "bidirectional"))
    )
    (net (code "9") (name "/LINKLED") (class "Default")
      (node (ref "R20") (pin "1") (pinfunction "1_1") (pintype "passive"))
      (node (ref "U1") (pin "25") (pinfunction "LINKLED_25") (pintype "output"))
    )
    (net (code "10") (name "/MISO") (class "Default")
      (node (ref "TP3") (pin "1") (pinfunction "1_1") (pintype "passive"))
      (node (ref "U1") (pin "34") (pinfunction "MISO_34") (pintype "output"))
      (node (ref "U2") (pin "77") (pinfunction "P0[8]/I2STX_WS/MISO1/MAT2[2]_77") (pintype "bidirectional"))
    )
    (net (code "11") (name "/MOSI") (class "Default")
      (node (ref "TP4") (pin "1") (pinfunction "1_1") (pintype "passive"))
      (node (ref "U1") (pin "35") (pinfunction "MOSI_35") (pintype "input"))
      (node (ref "U2") (pin "76") (pinfunction "P0[9]/I2STX_SDA/MOSI1/MAT2[3]_76") (pintype "bidirectional"))
    )
    (net (code "12") (name "/RD_N") (class "Default")
      (node (ref "C29") (pin "2") (pinfunction "2_2") (pintype "passive"))
      (node (ref "D5") (pin "4") (pinfunction "I/O_3_4") (pintype "passive"))
      (node (ref "T1") (pin "8") (pinfunction "RD-_8") (pintype "passive"))
    )
    (net (code "13") (name "/RD_P") (class "Default")
      (node (ref "C28") (pin "2") (pinfunction "2_2") (pintype "passive"))
      (node (ref "D5") (pin "6") (pinfunction "I/O_4_6") (pintype "passive"))
      (node (ref "T1") (pin "6") (pinfunction "RD+_6") (pintype "passive"))
    )
    (net (code "14") (name "/RXC_N") (class "Default")
      (node (ref "C29") (pin "1") (pinfunction "1_1") (pintype "passive"))
      (node (ref "R27") (pin "1") (pinfunction "1_1") (pintype "passive"))
      (node (ref "R29") (pin "2") (pinfunction "2_2") (pintype "passive"))
    )
    (net (code "15") (name "/RXC_P") (class "Default")
      (node (ref "C28") (pin "1") (pinfunction "1_1") (pintype "passive"))
      (node (ref "R26") (pin "1") (pinfunction "1_1") (pintype "passive"))
      (node (ref "R28") (pin "2") (pinfunction "2_2") (pintype "passive"))
    )
    (net (code "16") (name "/RX_N") (class "Default")
      (node (ref "J3") (pin "4") (pinfunction "4_4") (pintype "passive"))
      (node (ref "R33") (pin "2") (pinfunction "2_2") (pintype "passive"))
      (node (ref "T1") (pin "9") (pinfunction "RX-_9") (pintype "passive"))
    )
    (net (code "17") (name "/RX_P") (class "Default")
      (node (ref "J3") (pin "2") (pinfunction "2_2") (pintype "passive"))
      (node (ref "R31") (pin "1") (pinfunction "1_1") (pintype "passive"))
      (node (ref "T1") (pin "11") (pinfunction "RX+_11") (pintype "passive"))
    )
    (net (code "18") (name "/RX_PHY_N") (class "Default")
      (node (ref "R27") (pin "2") (pinfunction "2_2") (pintype "passive"))
      (node (ref "U1") (pin "5") (pinfunction "RXN_5") (pintype "input"))
    )
    (net (code "19") (name "/RX_PHY_P") (class "Default")
      (node (ref "R26") (pin "2") (pinfunction "2_2") (pintype "passive"))
      (node (ref "U1") (pin "6") (pinfunction "RXP_6") (pintype "input"))
    )
    (net (code "20") (name "/SCLK") (class "Default")
      (node (ref "TP2") (pin "1") (pinfunction "1_1") (pintype "passive"))
      (node (ref "U1") (pin "33") (pinfunction "SCLK_33") (pintype "input"))
      (node (ref "U2") (pin "78") (pinfunction "P0[7]/I2STX_CLK/SCK1/MAT2[1]_78") (pintype "bidirectional"))
    )
    (net (code "21") (name "/SWDCLK") (class "Default")
      (node (ref "J4") (pin "4") (pinfunction "4_4") (pintype "passive"))
      (node (ref "R16") (pin "1") (pinfunction "1_1") (pintype "passive"))
      (node (ref "U2") (pin "5") (pinfunction "TCK/SWDCLK_5") (pintype "input"))
    )
    (net (code "22") (name "/SWDIO") (class "Default")
      (node (ref "J4") (pin "2") (pinfunction "2_2") (pintype "passive"))
      (node (ref "U2") (pin "3") (pinfunction "TMS/SWDIO_3") (pintype "bidirectional"))
    )
    (net (code "23") (name "/SWO") (class "Default")
      (node (ref "J4") (pin "6") (pinfunction "6_6") (pintype "passive"))
      (node (ref "R15") (pin "2") (pinfunction "2_2") (pintype "passive"))
      (node (ref "U2") (pin "1") (pinfunction "TDO/SWO_1") (pintype "output"))
    )
    (net (code "24") (name "/TD_N") (class "Default")
      (node (ref "D5") (pin "1") (pinfunction "I/O_1_1") (pintype "passive"))
      (node (ref "R22") (pin "2") (pinfunction "2_2") (pintype "passive"))
      (node (ref "R25") (pin "1") (pinfunction "1_1") (pintype "passive"))
      (node (ref "T1") (pin "3") (pinfunction "TD-_3") (pintype "passive"))
    )
    (net (code "25") (name "/TD_P") (class "Default")
      (node (ref "D5") (pin "3") (pinfunction "I/O_2_3") (pintype "passive"))
      (node (ref "R21") (pin "2") (pinfunction "2_2") (pintype "passive"))
      (node (ref "R24") (pin "1") (pinfunction "1_1") (pintype "passive"))
      (node (ref "T1") (pin "1") (pinfunction "TD+_1") (pintype "passive"))
    )
    (net (code "26") (name "/TX_N") (class "Default")
      (node (ref "J3") (pin "3") (pinfunction "3_3") (pintype "passive"))
      (node (ref "T1") (pin "14") (pinfunction "TX-_14") (pintype "passive"))
    )
    (net (code "27") (name "/TX_P") (class "Default")
      (node (ref "J3") (pin "1") (pinfunction "1_1") (pintype "passive"))
      (node (ref "T1") (pin "16") (pinfunction "TX+_16") (pintype "passive"))
    )
    (net (code "28") (name "/TX_PHY_N") (class "Default")
      (node (ref "R25") (pin "2") (pinfunction "2_2") (pintype "passive"))
      (node (ref "U1") (pin "1") (pinfunction "TXN_1") (pintype "output"))
    )
    (net (code "29") (name "/TX_PHY_P") (class "Default")
      (node (ref "R24") (pin "2") (pinfunction "2_2") (pintype "passive"))
      (node (ref "U1") (pin "2") (pinfunction "TXP_2") (pintype "output"))
    )
    (net (code "30") (name "/UART_RX") (class "Default")
      (node (ref "J2") (pin "4") (pinfunction "4_4") (pintype "passive"))
      (node (ref "U2") (pin "49") (pinfunction "P0[11]/RXD2/SCL2/MAT3[1]_49") (pintype "bidirectional"))
    )
    (net (code "31") (name "/UART_TX") (class "Default")
      (node (ref "J2") (pin "5") (pinfunction "5_5") (pintype "passive"))
      (node (ref "U2") (pin "48") (pinfunction "P0[10]/TXD2/SDA2/MAT3[0]_48") (pintype "bidirectional"))
    )
    (net (code "32") (name "/XI") (class "Default")
      (node (ref "C24") (pin "1") (pinfunction "1_1") (pintype "passive"))
      (node (ref "R13") (pin "1") (pinfunction "1_1") (pintype "passive"))
      (node (ref "U1") (pin "30") (pinfunction "XI_30") (pintype "input"))
      (node (ref "Y1") (pin "3") (pinfunction "OSC2_3") (pintype "passive"))
    )
    (net (code "33") (name "/XO") (class "Default")
      (node (ref "C23") (pin "1") (pinfunction "1_1") (pintype "passive"))
      (node (ref "R13") (pin "2") (pinfunction "2_2") (pintype "passive"))
      (node (ref "U1") (pin "31") (pinfunction "XO_31") (pintype "output"))
      (node (ref "Y1") (pin "1") (pinfunction "OSC1_1") (pintype "passive"))
    )
    (net (code "34") (name "/~{CS}") (class "Default")
      (node (ref "R34") (pin "2") (pinfunction "2_2") (pintype "passive"))
      (node (ref "TP1") (pin "1") (pinfunction "1_1") (pintype "passive"))
      (node (ref "U1") (pin "32") (pinfunction "~{SCSN}_32") (pintype "input"))
      (node (ref "U2") (pin "79") (pinfunction "P0[6]/I2SRX_SDA/SSEL1/MAT2[0]_79") (pintype "bidirectional"))
    )
    (net (code "35") (name "/~{INTN}") (class "Default")
      (node (ref "R2") (pin "2") (pinfunction "2_2") (pintype "passive"))
      (node (ref "TP6") (pin "1") (pinfunction "1_1") (pintype "passive"))
      (node (ref "U1") (pin "36") (pinfunction "~{INTN}_36") (pintype "input"))
      (node (ref "U2") (pin "51") (pinfunction "P2[12]/~{EINT2}/I2STX_WS_51") (pintype "bidirectional"))
    )
    (net (code "36") (name "/~{RESET}") (class "Default")
      (node (ref "C25") (pin "1") (pinfunction "1_1") (pintype "passive"))
      (node (ref "J4") (pin "10") (pinfunction "10_10") (pintype "passive"))
      (node (ref "R14") (pin "2") (pinfunction "2_2") (pintype "passive"))
      (node (ref "U2") (pin "17") (pinfunction "~{RESET}_17") (pintype "input"))
    )
    (net (code "37") (name "/~{WIZRST}") (class "Default")
      (node (ref "R1") (pin "2") (pinfunction "2_2") (pintype "passive"))
      (node (ref "U1") (pin "37") (pinfunction "~{RSTN}_37") (pintype "input"))
      (node (ref "U2") (pin "50") (pinfunction "P2[13]/~{EINT3}/I2STX_SDA_50") (pintype "bidirectional"))
    )
    (net (code "38") (name "CH_GND") (class "Default")
      (node (ref "C31") (pin "2") (pinfunction "2_2") (pintype "passive"))
      (node (ref "C32") (pin "2") (pinfunction "2_2") (pintype "passive"))
    )
    (net (code "39") (name "GND") (class "Default")
      (node (ref "C1") (pin "2") (pinfunction "2_2") (pintype "passive"))
      (node (ref "C10") (pin "2") (pinfunction "2_2") (pintype "passive"))
      (node (ref "C11") (pin "2") (pinfunction "2_2") (pintype "passive"))
      (node (ref "C12") (pin "2") (pinfunction "2_2") (pintype "passive"))
      (node (ref "C13") (pin "2") (pinfunction "2_2") (pintype "passive"))
      (node (ref "C14") (pin "2") (pinfunction "2_2") (pintype "passive"))
      (node (ref "C15") (pin "2") (pinfunction "2_2") (pintype "passive"))
      (node (ref "C16") (pin "2") (pinfunction "2_2") (pintype "passive"))
      (node (ref "C17") (pin "2") (pinfunction "2_2") (pintype "passive"))
      (node (ref "C18") (pin "2") (pinfunction "2_2") (pintype "passive"))
      (node (ref "C19") (pin "2") (pinfunction "2_2") (pintype "passive"))
      (node (ref "C2") (pin "1") (pinfunction "1_1") (pintype "passive"))
      (node (ref "C20") (pin "2") (pinfunction "2_2") (pintype "passive"))
      (node (ref "C21") (pin "2") (pinfunction "2_2") (pintype "passive"))
      (node (ref "C22") (pin "2") (pinfunction "2_2") (pintype "passive"))
      (node (ref "C23") (pin "2") (pinfunction "2_2") (pintype "passive"))
      (node (ref "C24") (pin "2") (pinfunction "2_2") (pintype "passive"))
      (node (ref "C25") (pin "2") (pinfunction "2_2") (pintype "passive"))
      (node (ref "C26") (pin "2") (pinfunction "2_2") (pintype "passive"))
      (node (ref "C27") (pin "2") (pinfunction "2_2") (pintype "passive"))
      (node (ref "C3") (pin "2") (pinfunction "2_2") (pintype "passive"))
      (node (ref "C30") (pin "2") (pinfunction "2_2") (pintype "passive"))
      (node (ref "C32") (pin "1") (pinfunction "1_1") (pintype "passive"))
      (node (ref "C4") (pin "2") (pinfunction "2_2") (pintype "passive"))
      (node (ref "C5") (pin "2") (pinfunction "2_2") (pintype "passive"))
      (node (ref "C6") (pin "2") (pinfunction "2_2") (pintype "passive"))
      (node (ref "C7") (pin "2") (pinfunction "2_2") (pintype "passive"))
      (node (ref "C8") (pin "2") (pinfunction "2_2") (pintype "passive"))
      (node (ref "C9") (pin "2") (pinfunction "2_2") (pintype "passive"))
      (node (ref "D1") (pin "2") (pinfunction "K_2") (pintype "passive"))
      (node (ref "D2") (pin "2") (pinfunction "K_2") (pintype "passive"))
      (node (ref "D3") (pin "2") (pinfunction "K_2") (pintype "passive"))
      (node (ref "D4") (pin "2") (pinfunction "K_2") (pintype "passive"))
      (node (ref "D5") (pin "2") (pinfunction "GND_2") (pintype "passive"))
      (node (ref "J1") (pin "2") (pinfunction "2_2") (pintype "passive"))
      (node (ref "J2") (pin "1") (pinfunction "1_1") (pintype "passive"))
      (node (ref "J4") (pin "3") (pinfunction "3_3") (pintype "passive"))
      (node (ref "J4") (pin "5") (pinfunction "5_5") (pintype "passive"))
      (node (ref "J4") (pin "9") (pinfunction "9_9") (pintype "passive"))
      (node (ref "R10") (pin "2") (pinfunction "2_2") (pintype "passive"))
      (node (ref "R11") (pin "2") (pinfunction "2_2") (pintype "passive"))
      (node (ref "R12") (pin "2") (pinfunction "2_2") (pintype "passive"))
      (node (ref "R16") (pin "2") (pinfunction "2_2") (pintype "passive"))
      (node (ref "R6") (pin "2") (pinfunction "2_2") (pintype "passive"))
      (node (ref "R7") (pin "2") (pinfunction "2_2") (pintype "passive"))
      (node (ref "R8") (pin "2") (pinfunction "2_2") (pintype "passive"))
      (node (ref "R9") (pin "2") (pinfunction "2_2") (pintype "passive"))
      (node (ref "U1") (pin "14") (pinfunction "AGND_14") (pintype "power_in"))
      (node (ref "U1") (pin "16") (pinfunction "AGND_16") (pintype "power_in"))
      (node (ref "U1") (pin "19") (pinfunction "AGND_19") (pintype "power_in"))
      (node (ref "U1") (pin "29") (pinfunction "GND_29") (pintype "passive"))
      (node (ref "U1") (pin "3") (pinfunction "AGND_3") (pintype "power_in"))
      (node (ref "U1") (pin "48") (pinfunction "AGND_48") (pintype "power_in"))
      (node (ref "U1") (pin "9") (pinfunction "AGND_9") (pintype "power_in"))
      (node (ref "U2") (pin "11") (pinfunction "VSSA_11") (pintype "power_in"))
      (node (ref "U2") (pin "15") (pinfunction "VREFN_15") (pintype "power_in"))
      (node (ref "U2") (pin "16") (pinfunction "RTCX1_16") (pintype "input"))
      (node (ref "U2") (pin "22") (pinfunction "XTAL1_22") (pintype "passive"))
      (node (ref "U2") (pin "31") (pinfunction "VSS_31") (pintype "power_in"))
      (node (ref "U2") (pin "41") (pinfunction "VSS_41") (pintype "power_in"))
      (node (ref "U2") (pin "55") (pinfunction "VSS_55") (pintype "power_in"))
      (node (ref "U2") (pin "72") (pinfunction "VSS_72") (pintype "power_in"))
      (node (ref "U2") (pin "83") (pinfunction "VSS_83") (pintype "power_in"))
      (node (ref "U2") (pin "97") (pinfunction "VSS_97") (pintype "power_in"))
      (node (ref "U3") (pin "2") (pinfunction "GND_2") (pintype "power_in"))
      (node (ref "U3") (pin "4") (pinfunction "GND_4") (pintype "power_in"))
      (node (ref "Y1") (pin "2") (pinfunction "GND1_2") (pintype "passive"))
      (node (ref "Y1") (pin "4") (pinfunction "GND2_4") (pintype "passive"))
    )
    (net (code "40") (name "Net-(C31-Pad1)") (class "Default")
      (node (ref "C31") (pin "1") (pinfunction "1_1") (pintype "passive"))
      (node (ref "R30") (pin "2") (pinfunction "2_2") (pintype "passive"))
      (node (ref "R31") (pin "2") (pinfunction "2_2") (pintype "passive"))
      (node (ref "R32") (pin "2") (pinfunction "2_2") (pintype "passive"))
      (node (ref "R33") (pin "1") (pinfunction "1_1") (pintype "passive"))
    )
    (net (code "41") (name "Net-(D1-A)") (class "Default")
      (node (ref "D1") (pin "1") (pinfunction "A_1") (pintype "passive"))
      (node (ref "R17") (pin "1") (pinfunction "1_1") (pintype "passive"))
    )
    (net (code "42") (name "Net-(D2-A)") (class "Default")
      (node (ref "D2") (pin "1") (pinfunction "A_1") (pintype "passive"))
      (node (ref "R18") (pin "2") (pinfunction "2_2") (pintype "passive"))
    )
    (net (code "43") (name "Net-(D3-A)") (class "Default")
      (node (ref "D3") (pin "1") (pinfunction "A_1") (pintype "passive"))
      (node (ref "R19") (pin "2") (pinfunction "2_2") (pintype "passive"))
    )
    (net (code "44") (name "Net-(D4-A)") (class "Default")
      (node (ref "D4") (pin "1") (pinfunction "A_1") (pintype "passive"))
      (node (ref "R20") (pin "2") (pinfunction "2_2") (pintype "passive"))
    )
    (net (code "45") (name "Net-(T1-CRX)") (class "Default")
      (node (ref "R32") (pin "1") (pinfunction "1_1") (pintype "passive"))
      (node (ref "T1") (pin "10") (pinfunction "CRX_10") (pintype "passive"))
    )
    (net (code "46") (name "Net-(T1-CTX)") (class "Default")
      (node (ref "R30") (pin "1") (pinfunction "1_1") (pintype "passive"))
      (node (ref "T1") (pin "15") (pinfunction "CTX_15") (pintype "passive"))
    )
    (net (code "47") (name "Net-(U1-1V2O)") (class "Default")
      (node (ref "C22") (pin "1") (pinfunction "1_1") (pintype "passive"))
      (node (ref "U1") (pin "22") (pinfunction "1V2O_22") (pintype "output"))
    )
    (net (code "48") (name "Net-(U1-EXRES1)") (class "Default")
      (node (ref "R6") (pin "1") (pinfunction "1_1") (pintype "passive"))
      (node (ref "U1") (pin "10") (pinfunction "EXRES1_10") (pintype "bidirectional"))
    )
    (net (code "49") (name "Net-(U1-PMODE0)") (class "Default")
      (node (ref "R3") (pin "1") (pinfunction "1_1") (pintype "passive"))
      (node (ref "U1") (pin "45") (pinfunction "PMODE0_45") (pintype "input"))
    )
    (net (code "50") (name "Net-(U1-PMODE1)") (class "Default")
      (node (ref "R4") (pin "1") (pinfunction "1_1") (pintype "passive"))
      (node (ref "U1") (pin "44") (pinfunction "PMODE1_44") (pintype "input"))
    )
    (net (code "51") (name "Net-(U1-PMODE2)") (class "Default")
      (node (ref "R5") (pin "1") (pinfunction "1_1") (pintype "passive"))
      (node (ref "U1") (pin "43") (pinfunction "PMODE2_43") (pintype "input"))
    )
    (net (code "52") (name "Net-(U1-RSVD1)") (class "Default")
      (node (ref "R7") (pin "1") (pinfunction "1_1") (pintype "passive"))
      (node (ref "U1") (pin "23") (pinfunction "RSVD1_23") (pintype "input"))
    )
    (net (code "53") (name "Net-(U1-RSVD2)") (class "Default")
      (node (ref "R8") (pin "1") (pinfunction "1_1") (pintype "passive"))
      (node (ref "U1") (pin "38") (pinfunction "RSVD2_38") (pintype "input"))
    )
    (net (code "54") (name "Net-(U1-RSVD3)") (class "Default")
      (node (ref "R9") (pin "1") (pinfunction "1_1") (pintype "passive"))
      (node (ref "U1") (pin "39") (pinfunction "RSVD3_39") (pintype "input"))
    )
    (net (code "55") (name "Net-(U1-RSVD4)") (class "Default")
      (node (ref "R10") (pin "1") (pinfunction "1_1") (pintype "passive"))
      (node (ref "U1") (pin "40") (pinfunction "RSVD4_40") (pintype "input"))
    )
    (net (code "56") (name "Net-(U1-RSVD5)") (class "Default")
      (node (ref "R11") (pin "1") (pinfunction "1_1") (pintype "passive"))
      (node (ref "U1") (pin "41") (pinfunction "RSVD5_41") (pintype "input"))
    )
    (net (code "57") (name "Net-(U1-RSVD6)") (class "Default")
      (node (ref "R12") (pin "1") (pinfunction "1_1") (pintype "passive"))
      (node (ref "U1") (pin "42") (pinfunction "RSVD6_42") (pintype "input"))
    )
    (net (code "58") (name "Net-(U1-TOCAP)") (class "Default")
      (node (ref "C21") (pin "1") (pinfunction "1_1") (pintype "passive"))
      (node (ref "U1") (pin "20") (pinfunction "TOCAP_20") (pintype "output"))
    )
    (net (code "59") (name "unconnected-(D5-VCC-Pad5)") (class "Default")
      (node (ref "D5") (pin "5") (pinfunction "VCC_5") (pintype "passive+no_connect"))
    )
    (net (code "60") (name "unconnected-(J2-Pad2)") (class "Default")
      (node (ref "J2") (pin "2") (pinfunction "2_2") (pintype "passive+no_connect"))
    )
    (net (code "61") (name "unconnected-(J2-Pad6)") (class "Default")
      (node (ref "J2") (pin "6") (pinfunction "6_6") (pintype "passive+no_connect"))
    )
    (net (code "62") (name "unconnected-(J4-Pad7)") (class "Default")
      (node (ref "J4") (pin "7") (pinfunction "7_7") (pintype "passive+no_connect"))
    )
    (net (code "63") (name "unconnected-(J4-Pad8)") (class "Default")
      (node (ref "J4") (pin "8") (pinfunction "8_8") (pintype "passive+no_connect"))
    )
    (net (code "64") (name "unconnected-(U1-DNC-Pad7)") (class "Default")
      (node (ref "U1") (pin "7") (pinfunction "DNC_7") (pintype "bidirectional+no_connect"))
    )
    (net (code "65") (name "unconnected-(U1-DUPLED-Pad26)") (class "Default")
      (node (ref "U1") (pin "26") (pinfunction "DUPLED_26") (pintype "output+no_connect"))
    )
    (net (code "66") (name "unconnected-(U1-SPDLED-Pad24)") (class "Default")
      (node (ref "U1") (pin "24") (pinfunction "SPDLED_24") (pintype "output+no_connect"))
    )
    (net (code "67") (name "unconnected-(U1-VBG-Pad18)") (class "Default")
      (node (ref "U1") (pin "18") (pinfunction "VBG_18") (pintype "output+no_connect"))
    )
    (net (code "68") (name "unconnected-(U2A-NC-Pad13)") (class "Default")
      (node (ref "U2") (pin "13") (pinfunction "NC_13") (pintype "passive+no_connect"))
    )
    (net (code "69") (name "unconnected-(U2A-P0[0]{slash}RD1{slash}TXD3{slash}SDA1-Pad46)") (class "Default")
      (node (ref "U2") (pin "46") (pinfunction "P0[0]/RD1/TXD3/SDA1_46") (pintype "bidirectional+no_connect"))
    )
    (net (code "70") (name "unconnected-(U2A-P0[1]{slash}TD1{slash}RXD3{slash}SCL1-Pad47)") (class "Default")
      (node (ref "U2") (pin "47") (pinfunction "P0[1]/TD1/RXD3/SCL1_47") (pintype "bidirectional+no_connect"))
    )
    (net (code "71") (name "unconnected-(U2A-P0[2]{slash}TXD0{slash}AD0[7]-Pad98)") (class "Default")
      (node (ref "U2") (pin "98") (pinfunction "P0[2]/TXD0/AD0[7]_98") (pintype "bidirectional+no_connect"))
    )
    (net (code "72") (name "unconnected-(U2A-P0[3]{slash}RXD0{slash}AD0[6]-Pad99)") (class "Default")
      (node (ref "U2") (pin "99") (pinfunction "P0[3]/RXD0/AD0[6]_99") (pintype "bidirectional+no_connect"))
    )
    (net (code "73") (name "unconnected-(U2A-P0[4]{slash}I2SRX_CLK{slash}RD2{slash}CAP2[0]-Pad81)") (class "Default")
      (node (ref "U2") (pin "81") (pinfunction "P0[4]/I2SRX_CLK/RD2/CAP2[0]_81") (pintype "bidirectional+no_connect"))
    )
    (net (code "74") (name "unconnected-(U2A-P0[5]{slash}I2SRX_WS{slash}TD2{slash}CAP2[1]-Pad80)") (class "Default")
      (node (ref "U2") (pin "80") (pinfunction "P0[5]/I2SRX_WS/TD2/CAP2[1]_80") (pintype "bidirectional+no_connect"))
    )
    (net (code "75") (name "unconnected-(U2A-P0[15]{slash}TXD1{slash}SCK0{slash}SCK-Pad62)") (class "Default")
      (node (ref "U2") (pin "62") (pinfunction "P0[15]/TXD1/SCK0/SCK_62") (pintype "bidirectional+no_connect"))
    )
    (net (code "76") (name "unconnected-(U2A-P0[16]{slash}RXD1{slash}SSEL0{slash}SSEL-Pad63)") (class "Default")
      (node (ref "U2") (pin "63") (pinfunction "P0[16]/RXD1/SSEL0/SSEL_63") (pintype "bidirectional+no_connect"))
    )
    (net (code "77") (name "unconnected-(U2A-P0[17]{slash}CTS1{slash}MISO0{slash}MISO-Pad61)") (class "Default")
      (node (ref "U2") (pin "61") (pinfunction "P0[17]/CTS1/MISO0/MISO_61") (pintype "bidirectional+no_connect"))
    )
    (net (code "78") (name "unconnected-(U2A-P0[18]{slash}DCD1{slash}MOSI0{slash}MOSI-Pad60)") (class "Default")
      (node (ref "U2") (pin "60") (pinfunction "P0[18]/DCD1/MOSI0/MOSI_60") (pintype "bidirectional+no_connect"))
    )
    (net (code "79") (name "unconnected-(U2A-P0[19]{slash}DSR1{slash}SDA1-Pad59)") (class "Default")
      (node (ref "U2") (pin "59") (pinfunction "P0[19]/DSR1/SDA1_59") (pintype "bidirectional+no_connect"))
    )
    (net (code "80") (name "unconnected-(U2A-P0[20]{slash}DTR1{slash}SCL1-Pad58)") (class "Default")
      (node (ref "U2") (pin "58") (pinfunction "P0[20]/DTR1/SCL1_58") (pintype "bidirectional+no_connect"))
    )
    (net (code "81") (name "unconnected-(U2A-P0[21]{slash}RI1{slash}RD1-Pad57)") (class "Default")
      (node (ref "U2") (pin "57") (pinfunction "P0[21]/RI1/RD1_57") (pintype "bidirectional+no_connect"))
    )
    (net (code "82") (name "unconnected-(U2A-P0[22]{slash}RTS1{slash}TD1-Pad56)") (class "Default")
      (node (ref "U2") (pin "56") (pinfunction "P0[22]/RTS1/TD1_56") (pintype "bidirectional+no_connect"))
    )
    (net (code "83") (name "unconnected-(U2A-P0[23]{slash}AD0[0]{slash}I2SRX_CLK{slash}CAP3[0]-Pad9)") (class "Default")
      (node (ref "U2") (pin "9") (pinfunction "P0[23]/AD0[0]/I2SRX_CLK/CAP3[0]_9") (pintype "bidirectional+no_connect"))
    )
    (net (code "84") (name "unconnected-(U2A-P0[24]{slash}AD0[1]{slash}I2SRX_WS{slash}CAP3[1]-Pad8)") (class "Default")
      (node (ref "U2") (pin "8") (pinfunction "P0[24]/AD0[1]/I2SRX_WS/CAP3[1]_8") (pintype "bidirectional+no_connect"))
    )
    (net (code "85") (name "unconnected-(U2A-P0[25]{slash}AD0[2]{slash}I2SRX_SDA{slash}TXD3-Pad7)") (class "Default")
      (node (ref "U2") (pin "7") (pinfunction "P0[25]/AD0[2]/I2SRX_SDA/TXD3_7") (pintype "bidirectional+no_connect"))
    )
    (net (code "86") (name "unconnected-(U2A-P0[26]{slash}AD0[3]{slash}AOUT{slash}RXD3-Pad6)") (class "Default")
      (node (ref "U2") (pin "6") (pinfunction "P0[26]/AD0[3]/AOUT/RXD3_6") (pintype "bidirectional+no_connect"))
    )
    (net (code "87") (name "unconnected-(U2A-P0[27]{slash}SDA0{slash}USB_SDA-Pad25)") (class "Default")
      (node (ref "U2") (pin "25") (pinfunction "P0[27]/SDA0/USB_SDA_25") (pintype "bidirectional+no_connect"))
    )
    (net (code "88") (name "unconnected-(U2A-P0[28]{slash}SCL0{slash}USB_SCL-Pad24)") (class "Default")
      (node (ref "U2") (pin "24") (pinfunction "P0[28]/SCL0/USB_SCL_24") (pintype "bidirectional+no_connect"))
    )
    (net (code "89") (name "unconnected-(U2A-P0[29]{slash}USB_D+-Pad29)") (class "Default")
      (node (ref "U2") (pin "29") (pinfunction "P0[29]/USB_D+_29") (pintype "bidirectional+no_connect"))
    )
    (net (code "90") (name "unconnected-(U2A-P0[30]{slash}USB_D--Pad30)") (class "Default")
      (node (ref "U2") (pin "30") (pinfunction "P0[30]/USB_D-_30") (pintype "bidirectional+no_connect"))
    )
    (net (code "91") (name "unconnected-(U2A-P1[0]{slash}ENET_TXD0-Pad95)") (class "Default")
      (node (ref "U2") (pin "95") (pinfunction "P1[0]/ENET_TXD0_95") (pintype "bidirectional+no_connect"))
    )
    (net (code "92") (name "unconnected-(U2A-P1[1]{slash}ENET_TXD1-Pad94)") (class "Default")
      (node (ref "U2") (pin "94") (pinfunction "P1[1]/ENET_TXD1_94") (pintype "bidirectional+no_connect"))
    )
    (net (code "93") (name "unconnected-(U2A-P1[4]{slash}ENET_TX_EN-Pad93)") (class "Default")
      (node (ref "U2") (pin "93") (pinfunction "P1[4]/ENET_TX_EN_93") (pintype "bidirectional+no_connect"))
    )
    (net (code "94") (name "unconnected-(U2A-P1[8]{slash}ENET_CRS-Pad92)") (class "Default")
      (node (ref "U2") (pin "92") (pinfunction "P1[8]/ENET_CRS_92") (pintype "bidirectional+no_connect"))
    )
    (net (code "95") (name "unconnected-(U2A-P1[9]{slash}ENET_RXD0-Pad91)") (class "Default")
      (node (ref "U2") (pin "91") (pinfunction "P1[9]/ENET_RXD0_91") (pintype "bidirectional+no_connect"))
    )
    (net (code "96") (name "unconnected-(U2A-P1[10]{slash}ENET_RXD1-Pad90)") (class "Default")
      (node (ref "U2") (pin "90") (pinfunction "P1[10]/ENET_RXD1_90") (pintype "bidirectional+no_connect"))
    )
    (net (code "97") (name "unconnected-(U2A-P1[14]{slash}ENET_RX_ER-Pad89)") (class "Default")
      (node (ref "U2") (pin "89") (pinfunction "P1[14]/ENET_RX_ER_89") (pintype "bidirectional+no_connect"))
    )
    (net (code "98") (name "unconnected-(U2A-P1[16]{slash}ENET_MDC-Pad87)") (class "Default")
      (node (ref "U2") (pin "87") (pinfunction "P1[16]/ENET_MDC_87") (pintype "bidirectional+no_connect"))
    )
    (net (code "99") (name "unconnected-(U2A-P1[17]{slash}ENET_MDIO-Pad86)") (class "Default")
      (node (ref "U2") (pin "86") (pinfunction "P1[17]/ENET_MDIO_86") (pintype "bidirectional+no_connect"))
    )
    (net (code "100") (name "unconnected-(U2A-P1[18]{slash}USB_UP_LED{slash}PWM1[1]{slash}CAP1[0]-Pad32)") (class "Default")
      (node (ref "U2") (pin "32") (pinfunction "P1[18]/USB_UP_LED/PWM1[1]/CAP1[0]_32") (pintype "bidirectional+no_connect"))
    )
    (net (code "101") (name "unconnected-(U2A-P1[19]{slash}MCOA0{slash}~{USB_PPWR}{slash}CAP1[1]-Pad33)") (class "Default")
      (node (ref "U2") (pin "33") (pinfunction "P1[19]/MCOA0/~{USB_PPWR}/CAP1[1]_33") (pintype "bidirectional+no_connect"))
    )
    (net (code "102") (name "unconnected-(U2A-P1[20]{slash}MCI0{slash}PWM1[2]{slash}SCK0-Pad34)") (class "Default")
      (node (ref "U2") (pin "34") (pinfunction "P1[20]/MCI0/PWM1[2]/SCK0_34") (pintype "bidirectional+no_connect"))
    )
    (net (code "103") (name "unconnected-(U2A-P1[21]{slash}~{MCABORT}{slash}PWM1[3]{slash}SSEL0-Pad35)") (class "Default")
      (node (ref "U2") (pin "35") (pinfunction "P1[21]/~{MCABORT}/PWM1[3]/SSEL0_35") (pintype "bidirectional+no_connect"))
    )
    (net (code "104") (name "unconnected-(U2A-P1[22]{slash}MCOB0{slash}USB_PWRD{slash}MAT1[0]-Pad36)") (class "Default")
      (node (ref "U2") (pin "36") (pinfunction "P1[22]/MCOB0/USB_PWRD/MAT1[0]_36") (pintype "bidirectional+no_connect"))
    )
    (net (code "105") (name "unconnected-(U2A-P1[23]{slash}MCI1{slash}PWM1[4]{slash}MISO0-Pad37)") (class "Default")
      (node (ref "U2") (pin "37") (pinfunction "P1[23]/MCI1/PWM1[4]/MISO0_37") (pintype "bidirectional+no_connect"))
    )
    (net (code "106") (name "unconnected-(U2A-P1[24]{slash}MCI2{slash}PWM1[5]{slash}MOSI0-Pad38)") (class "Default")
      (node (ref "U2") (pin "38") (pinfunction "P1[24]/MCI2/PWM1[5]/MOSI0_38") (pintype "bidirectional+no_connect"))
    )
    (net (code "107") (name "unconnected-(U2A-P1[25]{slash}MCOA1{slash}MAT1[1]-Pad39)") (class "Default")
      (node (ref "U2") (pin "39") (pinfunction "P1[25]/MCOA1/MAT1[1]_39") (pintype "bidirectional+no_connect"))
    )
    (net (code "108") (name "unconnected-(U2A-P1[26]{slash}MCOB1{slash}PWM1[6]{slash}CAP0[0]-Pad40)") (class "Default")
      (node (ref "U2") (pin "40") (pinfunction "P1[26]/MCOB1/PWM1[6]/CAP0[0]_40") (pintype "bidirectional+no_connect"))
    )
    (net (code "109") (name "unconnected-(U2A-P1[28]{slash}MCOA2{slash}PCAP1[0]{slash}MAT0[0]-Pad44)") (class "Default")
      (node (ref "U2") (pin "44") (pinfunction "P1[28]/MCOA2/PCAP1[0]/MAT0[0]_44") (pintype "bidirectional+no_connect"))
    )
    (net (code "110") (name "unconnected-(U2A-P1[29]{slash}MCOB2{slash}PCAP1[1]{slash}MAT0[1]-Pad45)") (class "Default")
      (node (ref "U2") (pin "45") (pinfunction "P1[29]/MCOB2/PCAP1[1]/MAT0[1]_45") (pintype "bidirectional+no_connect"))
    )
    (net (code "111") (name "unconnected-(U2A-P1[30]{slash}VBUS{slash}AD0[4]-Pad21)") (class "Default")
      (node (ref "U2") (pin "21") (pinfunction "P1[30]/VBUS/AD0[4]_21") (pintype "bidirectional+no_connect"))
    )
    (net (code "112") (name "unconnected-(U2A-P1[31]{slash}SCK1{slash}AD0[5]-Pad20)") (class "Default")
      (node (ref "U2") (pin "20") (pinfunction "P1[31]/SCK1/AD0[5]_20") (pintype "bidirectional+no_connect"))
    )
    (net (code "113") (name "unconnected-(U2A-P2[0]{slash}PWM1[1]{slash}TXD1-Pad75)") (class "Default")
      (node (ref "U2") (pin "75") (pinfunction "P2[0]/PWM1[1]/TXD1_75") (pintype "bidirectional+no_connect"))
    )
    (net (code "114") (name "unconnected-(U2A-P2[1]{slash}PWM1[2]{slash}RXD1-Pad74)") (class "Default")
      (node (ref "U2") (pin "74") (pinfunction "P2[1]/PWM1[2]/RXD1_74") (pintype "bidirectional+no_connect"))
    )
    (net (code "115") (name "unconnected-(U2A-P2[2]{slash}PWM1[3]{slash}CTS1{slash}TRACEDATA[3]-Pad73)") (class "Default")
      (node (ref "U2") (pin "73") (pinfunction "P2[2]/PWM1[3]/CTS1/TRACEDATA[3]_73") (pintype "bidirectional+no_connect"))
    )
    (net (code "116") (name "unconnected-(U2A-P2[3]{slash}PWM1[4]{slash}DCD1{slash}TRACEDATA[2]-Pad70)") (class "Default")
      (node (ref "U2") (pin "70") (pinfunction "P2[3]/PWM1[4]/DCD1/TRACEDATA[2]_70") (pintype "bidirectional+no_connect"))
    )
    (net (code "117") (name "unconnected-(U2A-P2[4]{slash}PWM1[5]{slash}DSR1{slash}TRACEDATA[1]-Pad69)") (class "Default")
      (node (ref "U2") (pin "69") (pinfunction "P2[4]/PWM1[5]/DSR1/TRACEDATA[1]_69") (pintype "bidirectional+no_connect"))
    )
    (net (code "118") (name "unconnected-(U2A-P2[5]{slash}PWM1[6]{slash}DTR1{slash}TRACEDATA[0]-Pad68)") (class "Default")
      (node (ref "U2") (pin "68") (pinfunction "P2[5]/PWM1[6]/DTR1/TRACEDATA[0]_68") (pintype "bidirectional+no_connect"))
    )
    (net (code "119") (name "unconnected-(U2A-P2[6]{slash}PCAP1[0]{slash}RI1{slash}TRACECLK-Pad67)") (class "Default")
      (node (ref "U2") (pin "67") (pinfunction "P2[6]/PCAP1[0]/RI1/TRACECLK_67") (pintype "bidirectional+no_connect"))
    )
    (net (code "120") (name "unconnected-(U2A-P2[7]{slash}RD2{slash}RTS1-Pad66)") (class "Default")
      (node (ref "U2") (pin "66") (pinfunction "P2[7]/RD2/RTS1_66") (pintype "bidirectional+no_connect"))
    )
    (net (code "121") (name "unconnected-(U2A-P2[8]{slash}TD2{slash}TXD2-Pad65)") (class "Default")
      (node (ref "U2") (pin "65") (pinfunction "P2[8]/TD2/TXD2_65") (pintype "bidirectional+no_connect"))
    )
    (net (code "122") (name "unconnected-(U2A-P2[9]{slash}USB_CONNECT{slash}RXD2-Pad64)") (class "Default")
      (node (ref "U2") (pin "64") (pinfunction "P2[9]/USB_CONNECT/RXD2_64") (pintype "bidirectional+no_connect"))
    )
    (net (code "123") (name "unconnected-(U2A-P2[10]{slash}~{EINT0}{slash}NMI-Pad53)") (class "Default")
      (node (ref "U2") (pin "53") (pinfunction "P2[10]/~{EINT0}/NMI_53") (pintype "bidirectional+no_connect"))
    )
    (net (code "124") (name "unconnected-(U2A-P2[11]{slash}~{EINT1}{slash}I2STX_CLK-Pad52)") (class "Default")
      (node (ref "U2") (pin "52") (pinfunction "P2[11]/~{EINT1}/I2STX_CLK_52") (pintype "bidirectional+no_connect"))
    )
    (net (code "125") (name "unconnected-(U2A-P3[25]{slash}MAT0[0]{slash}PWM1[2]-Pad27)") (class "Default")
      (node (ref "U2") (pin "27") (pinfunction "P3[25]/MAT0[0]/PWM1[2]_27") (pintype "bidirectional+no_connect"))
    )
    (net (code "126") (name "unconnected-(U2A-P3[26]{slash}STCLK{slash}MAT0[1]{slash}PWM1[3]-Pad26)") (class "Default")
      (node (ref "U2") (pin "26") (pinfunction "P3[26]/STCLK/MAT0[1]/PWM1[3]_26") (pintype "bidirectional+no_connect"))
    )
    (net (code "127") (name "unconnected-(U2A-P4[28]{slash}RX_MCLK{slash}MAT2[0]{slash}TXD3-Pad82)") (class "Default")
      (node (ref "U2") (pin "82") (pinfunction "P4[28]/RX_MCLK/MAT2[0]/TXD3_82") (pintype "bidirectional+no_connect"))
    )
    (net (code "128") (name "unconnected-(U2A-P4[29]{slash}TX_MCLK{slash}MAT2[1]{slash}RXD3-Pad85)") (class "Default")
      (node (ref "U2") (pin "85") (pinfunction "P4[29]/TX_MCLK/MAT2[1]/RXD3_85") (pintype "bidirectional+no_connect"))
    )
    (net (code "129") (name "unconnected-(U2A-RTCK-Pad100)") (class "Default")
      (node (ref "U2") (pin "100") (pinfunction "RTCK_100") (pintype "output+no_connect"))
    )
    (net (code "130") (name "unconnected-(U2A-RTCX2-Pad18)") (class "Default")
      (node (ref "U2") (pin "18") (pinfunction "RTCX2_18") (pintype "output+no_connect"))
    )
    (net (code "131") (name "unconnected-(U2A-TDI-Pad2)") (class "Default")
      (node (ref "U2") (pin "2") (pinfunction "TDI_2") (pintype "input+no_connect"))
    )
    (net (code "132") (name "unconnected-(U2A-XTAL2-Pad23)") (class "Default")
      (node (ref "U2") (pin "23") (pinfunction "XTAL2_23") (pintype "passive+no_connect"))
    )
    (net (code "133") (name "unconnected-(U2A-~{RSTOUT}-Pad14)") (class "Default")
      (node (ref "U2") (pin "14") (pinfunction "~{RSTOUT}_14") (pintype "output+no_connect"))
    )
    (net (code "134") (name "unconnected-(U2A-~{TRST}-Pad4)") (class "Default")
      (node (ref "U2") (pin "4") (pinfunction "~{TRST}_4") (pintype "input+no_connect"))
    )
  )
)
